# zxld383-boost-driver-13mm.net
KiCad netlist of a schematic drawn in EAGLE
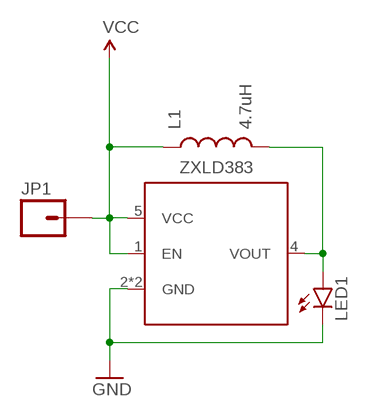
[diagram p0: schematic, sheet 1]

(export (version "E")
  (design (tool "Eeschema 10.0.6"))
  (components
    (comp (ref "JP1")
      (value "M01NOT-A-VIA-NOPE")
      (footprint "eagle-import:1X01_NOSILK_NOSTOP")
      (libsource (lib "eagle-import") (part "M01NOT-A-VIA-NOPE"))
    )
    (comp (ref "L1")
      (value "4.7uH")
      (footprint "eagle-import:1007")
      (libsource (lib "eagle-import") (part "INDUCTOR1007"))
    )
    (comp (ref "LED1")
      (value "LED10MM")
      (footprint "eagle-import:LED10MM")
      (libsource (lib "eagle-import") (part "LED10MM"))
    )
    (comp (ref "ZXLD383")
      (value "ZXLD383")
      (footprint "eagle-import:TSOT-23-5")
      (libsource (lib "eagle-import") (part "ZXLD383"))
    )
  )
  (nets
    (net (code "1") (name "GND") (class "Default")
      (node (ref "LED1") (pin "C") (pinfunction "C_C") (pintype "passive"))
      (node (ref "ZXLD383") (pin "2") (pinfunction "GND_2") (pintype "bidirectional"))
      (node (ref "ZXLD383") (pin "3") (pinfunction "GND_3") (pintype "bidirectional"))
    )
    (net (code "2") (name "Net-(ZXLD383-VOUT)") (class "Default")
      (node (ref "L1") (pin "2") (pinfunction "2_2") (pintype "passive"))
      (node (ref "LED1") (pin "A") (pinfunction "A_A") (pintype "passive"))
      (node (ref "ZXLD383") (pin "4") (pinfunction "VOUT_4") (pintype "bidirectional"))
    )
    (net (code "3") (name "VCC") (class "Default")
      (node (ref "JP1") (pin "P$1") (pinfunction "1_P$1") (pintype "passive"))
      (node (ref "L1") (pin "1") (pinfunction "1_1") (pintype "passive"))
      (node (ref "ZXLD383") (pin "1") (pinfunction "EN_1") (pintype "bidirectional"))
      (node (ref "ZXLD383") (pin "5") (pinfunction "VCC_5") (pintype "bidirectional"))
    )
  )
)
